# Audi_Amp.net
KiCad netlist of a schematic drawn in EAGLE
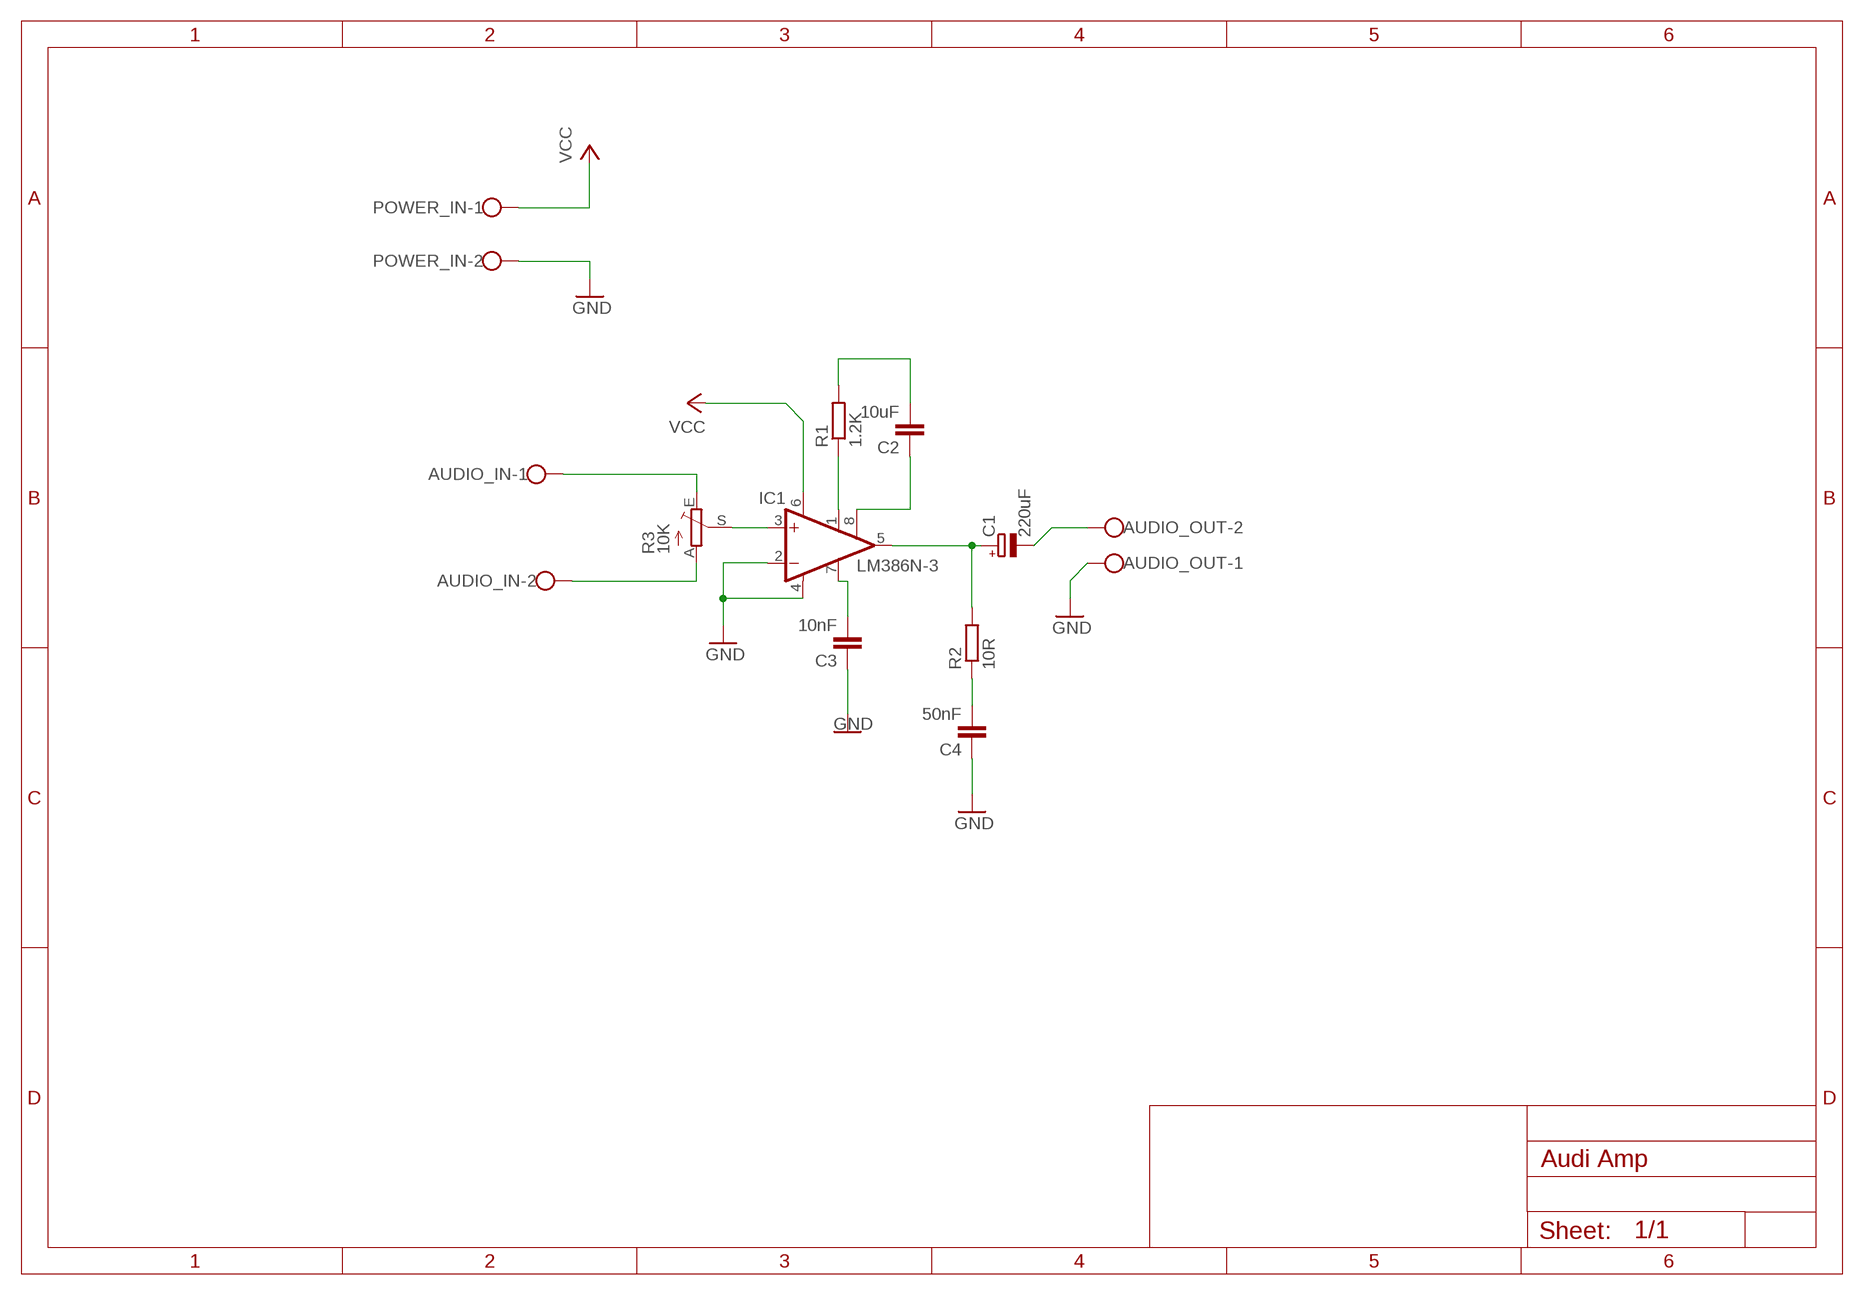
[diagram p0: schematic, sheet 1]

(export (version "E")
  (design (tool "Eeschema 10.0.6"))
  (components
    (comp (ref "AUDIO_IN")
      (value "W237-102")
      (footprint "eagle-import:W237-102")
      (fields (field (name "MPN") "237-102"))
      (libsource (lib "eagle-import") (part "W237-102"))
    )
    (comp (ref "AUDIO_OUT")
      (value "W237-102")
      (footprint "eagle-import:W237-102")
      (fields (field (name "MPN") "237-102"))
      (libsource (lib "eagle-import") (part "W237-102"))
    )
    (comp (ref "C1")
      (value "220uF")
      (footprint "eagle-import:E3,5-8")
      (libsource (lib "eagle-import") (part "CPOL-EUE3.5-8"))
    )
    (comp (ref "C2")
      (value "10uF")
      (footprint "eagle-import:C075-032X103")
      (libsource (lib "eagle-import") (part "C-EU075-032X103"))
    )
    (comp (ref "C3")
      (value "10nF")
      (footprint "eagle-import:C075-032X103")
      (libsource (lib "eagle-import") (part "C-EU075-032X103"))
    )
    (comp (ref "C4")
      (value "50nF")
      (footprint "eagle-import:C075-032X103")
      (libsource (lib "eagle-import") (part "C-EU075-032X103"))
    )
    (comp (ref "IC1")
      (value "LM386N-3")
      (footprint "eagle-import:DIL08")
      (libsource (lib "eagle-import") (part "LM386?-N3"))
    )
    (comp (ref "POWER_IN")
      (value "W237-102")
      (footprint "eagle-import:W237-102")
      (fields (field (name "MPN") "237-102"))
      (libsource (lib "eagle-import") (part "W237-102"))
    )
    (comp (ref "R1")
      (value "1.2K")
      (footprint "eagle-import:0204_7")
      (libsource (lib "eagle-import") (part "R-EU_0204/7"))
    )
    (comp (ref "R2")
      (value "10R")
      (footprint "eagle-import:0204_7")
      (libsource (lib "eagle-import") (part "R-EU_0204/7"))
    )
    (comp (ref "R3")
      (value "10K")
      (footprint "eagle-import:B64Y")
      (libsource (lib "eagle-import") (part "TRIM_EU-B64Y"))
    )
  )
  (nets
    (net (code "1") (name "GND") (class "Default")
      (node (ref "AUDIO_OUT") (pin "1") (pinfunction "KL_1") (pintype "passive"))
      (node (ref "C3") (pin "1") (pinfunction "1_1") (pintype "passive"))
      (node (ref "C4") (pin "1") (pinfunction "1_1") (pintype "passive"))
      (node (ref "IC1") (pin "2") (pinfunction "-IN_2") (pintype "input"))
      (node (ref "IC1") (pin "4") (pinfunction "GND_4") (pintype "power_in"))
      (node (ref "POWER_IN") (pin "2") (pinfunction "KL_2") (pintype "passive"))
    )
    (net (code "2") (name "Net-(AUDIO_INA-KL)") (class "Default")
      (node (ref "AUDIO_IN") (pin "1") (pinfunction "KL_1") (pintype "passive"))
      (node (ref "R3") (pin "E") (pinfunction "E_E") (pintype "passive"))
    )
    (net (code "3") (name "Net-(AUDIO_INB-KL)") (class "Default")
      (node (ref "AUDIO_IN") (pin "2") (pinfunction "KL_2") (pintype "passive"))
      (node (ref "R3") (pin "A") (pinfunction "A_A") (pintype "passive"))
    )
    (net (code "4") (name "Net-(AUDIO_OUTB-KL)") (class "Default")
      (node (ref "AUDIO_OUT") (pin "2") (pinfunction "KL_2") (pintype "passive"))
      (node (ref "C1") (pin "-") (pinfunction "-_-") (pintype "passive"))
    )
    (net (code "5") (name "Net-(C2-Pad1)") (class "Default")
      (node (ref "C2") (pin "1") (pinfunction "1_1") (pintype "passive"))
      (node (ref "IC1") (pin "8") (pinfunction "GAIN_8") (pintype "passive"))
    )
    (net (code "6") (name "Net-(C2-Pad2)") (class "Default")
      (node (ref "C2") (pin "2") (pinfunction "2_2") (pintype "passive"))
      (node (ref "R1") (pin "2") (pinfunction "2_2") (pintype "passive"))
    )
    (net (code "7") (name "Net-(C4-Pad2)") (class "Default")
      (node (ref "C4") (pin "2") (pinfunction "2_2") (pintype "passive"))
      (node (ref "R2") (pin "1") (pinfunction "1_1") (pintype "passive"))
    )
    (net (code "8") (name "Net-(IC1-+IN)") (class "Default")
      (node (ref "IC1") (pin "3") (pinfunction "+IN_3") (pintype "input"))
      (node (ref "R3") (pin "S") (pinfunction "S_S") (pintype "passive"))
    )
    (net (code "9") (name "Net-(IC1-BYPASS)") (class "Default")
      (node (ref "C3") (pin "2") (pinfunction "2_2") (pintype "passive"))
      (node (ref "IC1") (pin "7") (pinfunction "BYPASS_7") (pintype "passive"))
    )
    (net (code "10") (name "Net-(IC1-GAIN-Pad1)") (class "Default")
      (node (ref "IC1") (pin "1") (pinfunction "GAIN_1") (pintype "passive"))
      (node (ref "R1") (pin "1") (pinfunction "1_1") (pintype "passive"))
    )
    (net (code "11") (name "Net-(IC1-OUT)") (class "Default")
      (node (ref "C1") (pin "+") (pinfunction "+_+") (pintype "passive"))
      (node (ref "IC1") (pin "5") (pinfunction "OUT_5") (pintype "output"))
      (node (ref "R2") (pin "2") (pinfunction "2_2") (pintype "passive"))
    )
    (net (code "12") (name "VCC") (class "Default")
      (node (ref "IC1") (pin "6") (pinfunction "VS_6") (pintype "power_in"))
      (node (ref "POWER_IN") (pin "1") (pinfunction "KL_1") (pintype "passive"))
    )
  )
)
